# Sensor_Box_CAN_Switch_STM.net
KiCad netlist of a schematic drawn in Altium Designer
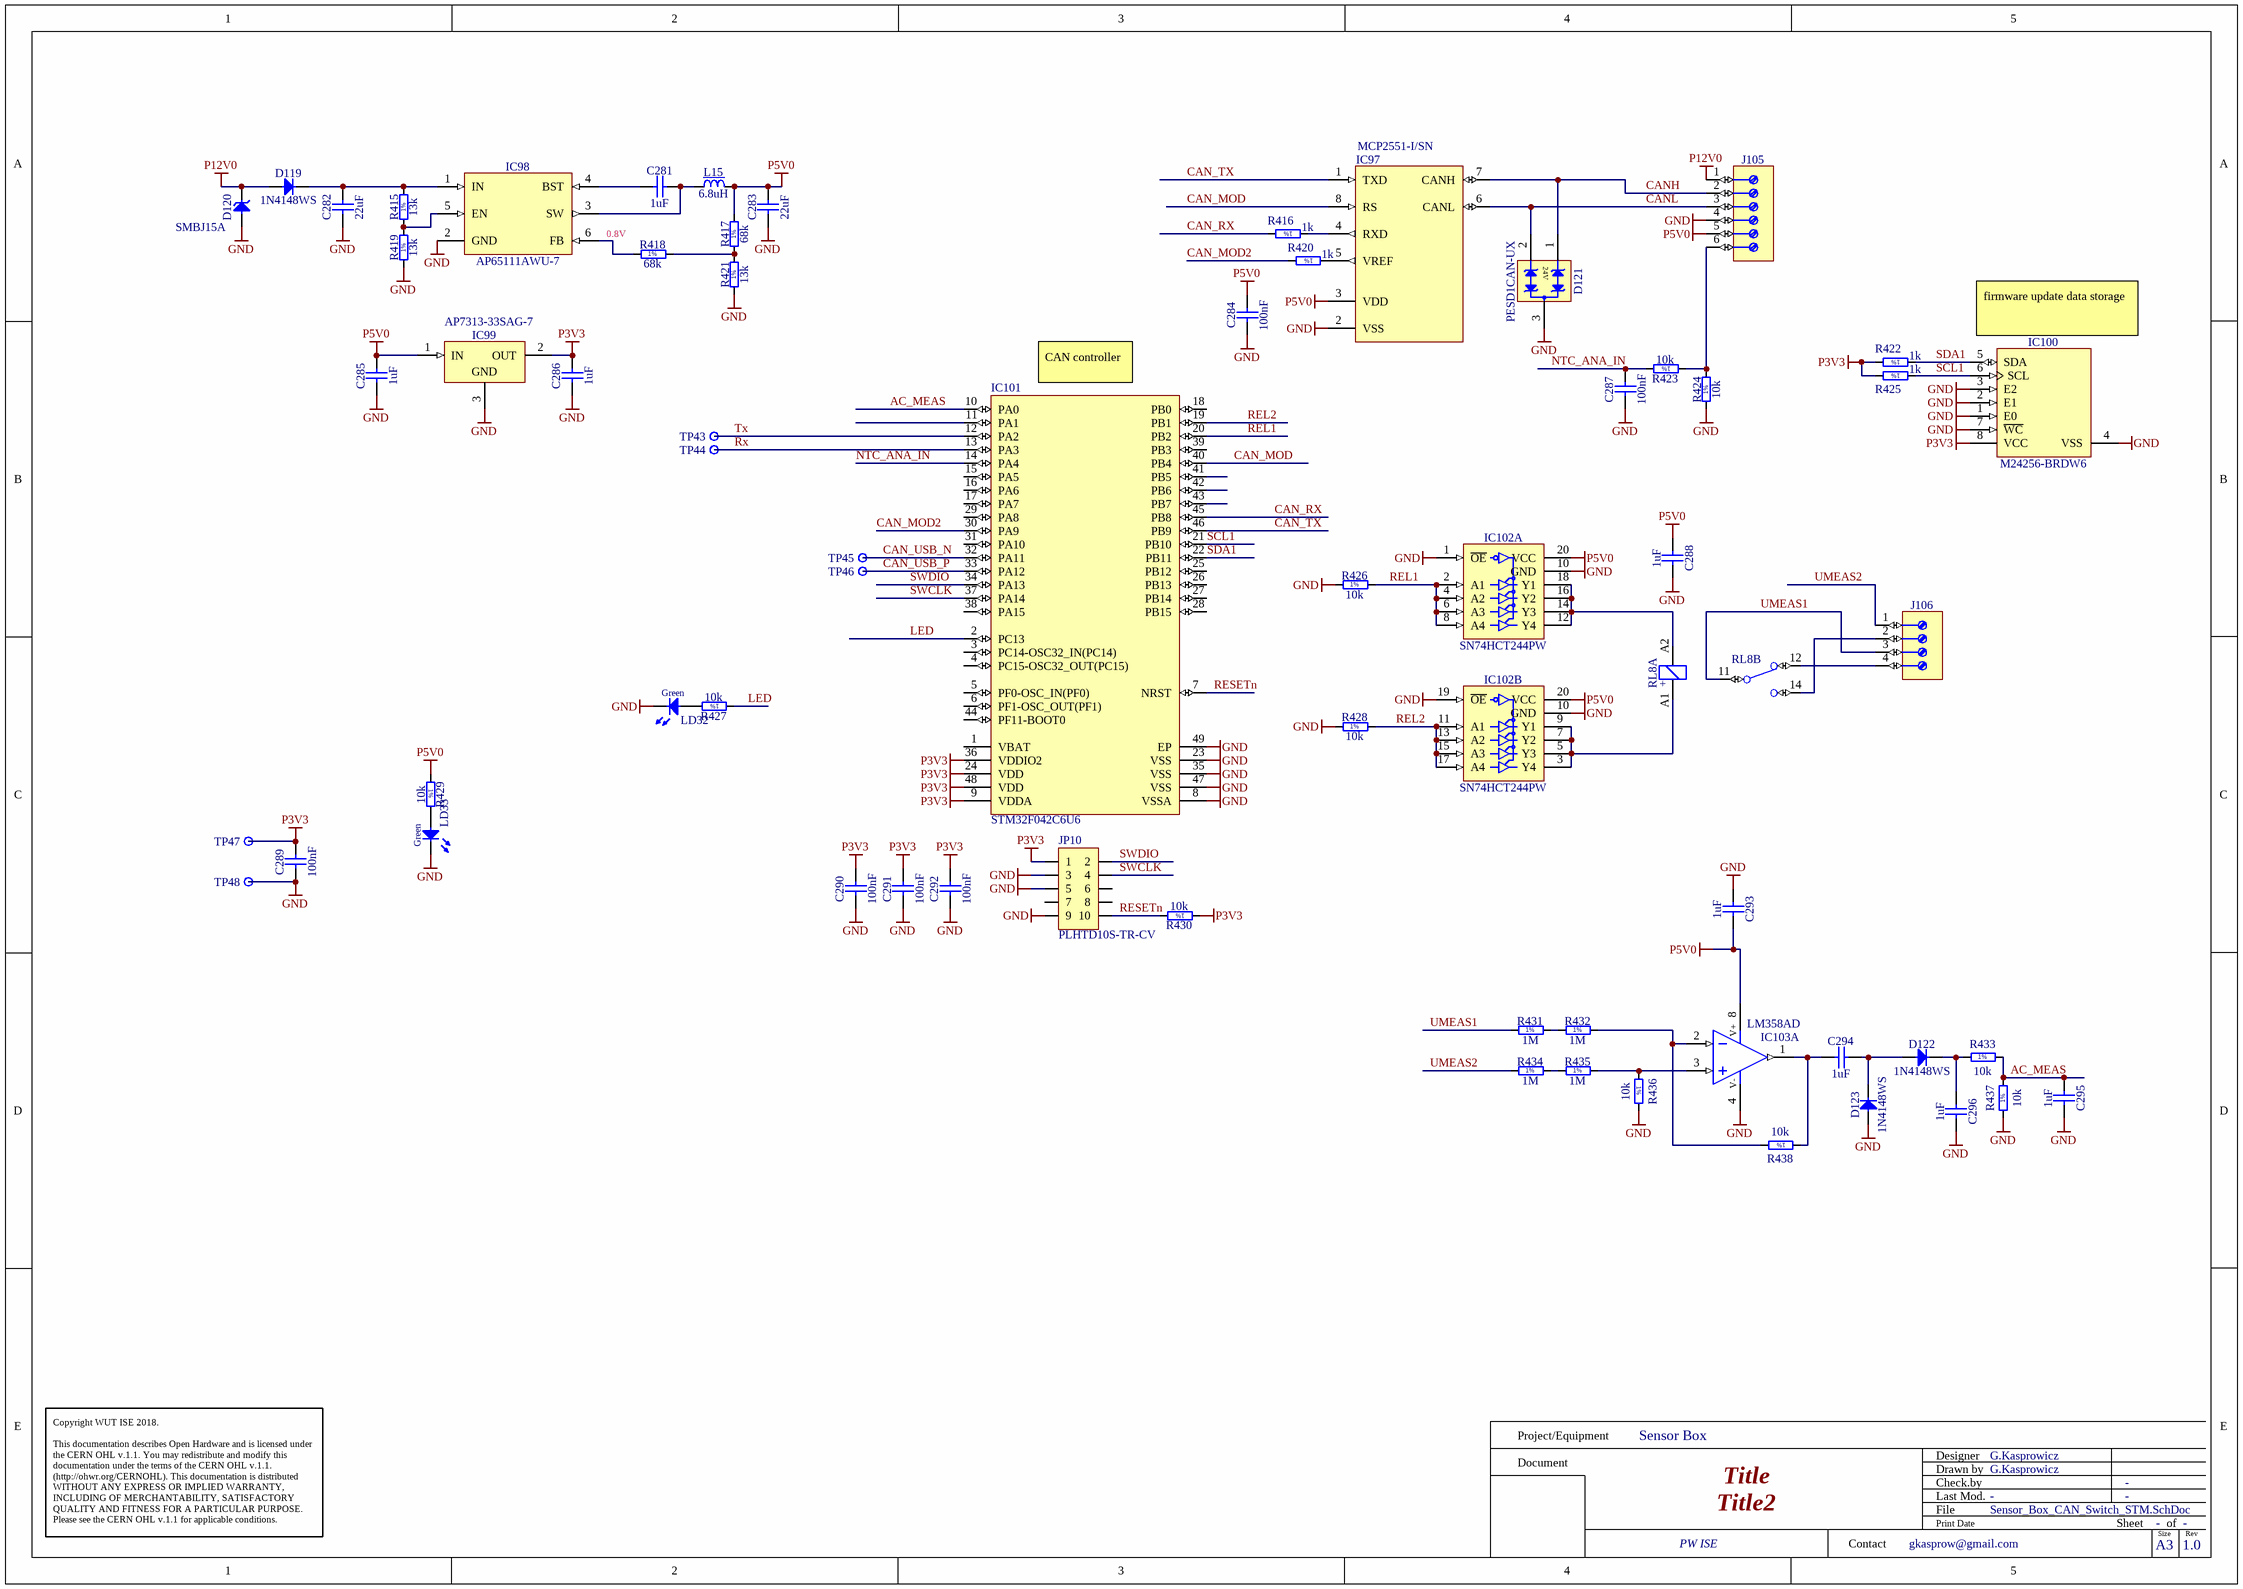
[diagram p0: Sensor_Box_CAN_Switch_STM.SchDoc]

(export (version "E")
  (design (tool "Eeschema 10.0.6"))
  (components
    (comp (ref "C281")
      (value "1uF")
      (footprint "CAPC1005X55N")
      (description "Non-polarised capacitor")
      (fields
        (field (name "PART NUMBER") "CC0402_1UF_16V_10%_X5R")
        (field (name "VOLTAGE") "16V")
        (field (name "AUTHOR") "CERN DEM JLC")
      )
      (libsource (lib "Capacitors") (part "Capacitor - non polarized"))
    )
    (comp (ref "C282")
      (value "22uF")
      (footprint "CAPC1709X100N")
      (description "Non-polarised capacitor")
      (fields
        (field (name "PART NUMBER") "CC0603_22UF_6.3V_20%_X5R")
        (field (name "VOLTAGE") "6.3V")
        (field (name "AUTHOR") "CERN DEM JLC")
      )
      (libsource (lib "Capacitors") (part "Capacitor - non polarized"))
    )
    (comp (ref "C283")
      (value "22uF")
      (footprint "CAPC1709X100N")
      (description "Non-polarised capacitor")
      (fields
        (field (name "PART NUMBER") "CC0603_22UF_6.3V_20%_X5R")
        (field (name "VOLTAGE") "6.3V")
        (field (name "AUTHOR") "CERN DEM JLC")
      )
      (libsource (lib "Capacitors") (part "Capacitor - non polarized"))
    )
    (comp (ref "C284")
      (value "100nF")
      (footprint "CAPC1005X55N")
      (description "Non-polarised capacitor")
      (fields
        (field (name "PART NUMBER") "CC0402_100NF_16V_10%_X5R")
        (field (name "VOLTAGE") "16V")
        (field (name "AUTHOR") "CERN DEM JLC")
      )
      (libsource (lib "Capacitors") (part "Capacitor - non polarized"))
    )
    (comp (ref "C285")
      (value "1uF")
      (footprint "CAPC1005X55N")
      (description "Non-polarised capacitor")
      (fields
        (field (name "PART NUMBER") "CC0402_1UF_16V_10%_X5R")
        (field (name "VOLTAGE") "16V")
        (field (name "AUTHOR") "CERN DEM JLC")
      )
      (libsource (lib "Capacitors") (part "Capacitor - non polarized"))
    )
    (comp (ref "C286")
      (value "1uF")
      (footprint "CAPC1005X55N")
      (description "Non-polarised capacitor")
      (fields
        (field (name "PART NUMBER") "CC0402_1UF_16V_10%_X5R")
        (field (name "VOLTAGE") "16V")
        (field (name "AUTHOR") "CERN DEM JLC")
      )
      (libsource (lib "Capacitors") (part "Capacitor - non polarized"))
    )
    (comp (ref "C287")
      (value "100nF")
      (footprint "CAPC1005X55N")
      (description "Non-polarised capacitor")
      (fields
        (field (name "PART NUMBER") "CC0402_100NF_16V_10%_X5R")
        (field (name "VOLTAGE") "16V")
        (field (name "AUTHOR") "CERN DEM JLC")
      )
      (libsource (lib "Capacitors") (part "Capacitor - non polarized"))
    )
    (comp (ref "C288")
      (value "1uF")
      (footprint "CAPC1005X55N")
      (description "Non-polarised capacitor")
      (fields
        (field (name "PART NUMBER") "CC0402_1UF_16V_10%_X5R")
        (field (name "VOLTAGE") "16V")
        (field (name "AUTHOR") "CERN DEM JLC")
      )
      (libsource (lib "Capacitors") (part "Capacitor - non polarized"))
    )
    (comp (ref "C289")
      (value "100nF")
      (footprint "CAPC1005X55N")
      (description "Non-polarised capacitor")
      (fields
        (field (name "PART NUMBER") "CC0402_100NF_16V_10%_X5R")
        (field (name "VOLTAGE") "16V")
        (field (name "AUTHOR") "CERN DEM JLC")
      )
      (libsource (lib "Capacitors") (part "Capacitor - non polarized"))
    )
    (comp (ref "C290")
      (value "100nF")
      (footprint "CAPC1005X55N")
      (description "Non-polarised capacitor")
      (fields
        (field (name "PART NUMBER") "CC0402_100NF_16V_10%_X5R")
        (field (name "VOLTAGE") "16V")
        (field (name "AUTHOR") "CERN DEM JLC")
      )
      (libsource (lib "Capacitors") (part "Capacitor - non polarized"))
    )
    (comp (ref "C291")
      (value "100nF")
      (footprint "CAPC1005X55N")
      (description "Non-polarised capacitor")
      (fields
        (field (name "PART NUMBER") "CC0402_100NF_16V_10%_X5R")
        (field (name "VOLTAGE") "16V")
        (field (name "AUTHOR") "CERN DEM JLC")
      )
      (libsource (lib "Capacitors") (part "Capacitor - non polarized"))
    )
    (comp (ref "C292")
      (value "100nF")
      (footprint "CAPC1005X55N")
      (description "Non-polarised capacitor")
      (fields
        (field (name "PART NUMBER") "CC0402_100NF_16V_10%_X5R")
        (field (name "VOLTAGE") "16V")
        (field (name "AUTHOR") "CERN DEM JLC")
      )
      (libsource (lib "Capacitors") (part "Capacitor - non polarized"))
    )
    (comp (ref "C293")
      (value "1uF")
      (footprint "CAPC1005X55N")
      (description "Non-polarised capacitor")
      (fields
        (field (name "PART NUMBER") "CC0402_1UF_16V_10%_X5R")
        (field (name "VOLTAGE") "16V")
        (field (name "AUTHOR") "CERN DEM JLC")
      )
      (libsource (lib "Capacitors") (part "Capacitor - non polarized"))
    )
    (comp (ref "C294")
      (value "1uF")
      (footprint "CAPC1005X55N")
      (description "Non-polarised capacitor")
      (fields
        (field (name "PART NUMBER") "CC0402_1UF_16V_10%_X5R")
        (field (name "VOLTAGE") "16V")
        (field (name "AUTHOR") "CERN DEM JLC")
      )
      (libsource (lib "Capacitors") (part "Capacitor - non polarized"))
    )
    (comp (ref "C295")
      (value "1uF")
      (footprint "CAPC1005X55N")
      (description "Non-polarised capacitor")
      (fields
        (field (name "PART NUMBER") "CC0402_1UF_16V_10%_X5R")
        (field (name "VOLTAGE") "16V")
        (field (name "AUTHOR") "CERN DEM JLC")
      )
      (libsource (lib "Capacitors") (part "Capacitor - non polarized"))
    )
    (comp (ref "C296")
      (value "1uF")
      (footprint "CAPC1005X55N")
      (description "Non-polarised capacitor")
      (fields
        (field (name "PART NUMBER") "CC0402_1UF_16V_10%_X5R")
        (field (name "VOLTAGE") "16V")
        (field (name "AUTHOR") "CERN DEM JLC")
      )
      (libsource (lib "Capacitors") (part "Capacitor - non polarized"))
    )
    (comp (ref "D119")
      (value "1N4148WS")
      (footprint "SODFL2512X100N")
      (description "Diode")
      (fields
        (field (name "VOLTAGE") "75V")
        (field (name "POWER") "150mA")
        (field (name "AUTHOR") "CERN DEM JLC")
      )
      (libsource (lib "ICs And Semiconductors") (part "Diode"))
    )
    (comp (ref "D120")
      (value "SMBJ15A")
      (footprint "DIOM5336X265N")
      (description "Zener Diode")
      (fields
        (field (name "VOLTAGE") "15V")
        (field (name "POWER") "600W")
        (field (name "AUTHOR") "CERN DEM JLC")
      )
      (libsource (lib "ICs And Semiconductors") (part "Diode Zener"))
    )
    (comp (ref "D121")
      (value "PESD1CAN-UX")
      (footprint "SOT95P237X112-3N")
      (description "TVS Diode for CAN")
      (fields
        (field (name "VOLTAGE") "24V")
        (field (name "POWER") "400W")
        (field (name "AUTHOR") "CERN DEM JLC")
      )
      (libsource (lib "LIBRARY_SCH") (part "D_TVS_PESD1CAN"))
    )
    (comp (ref "D122")
      (value "1N4148WS")
      (footprint "SODFL2512X100N")
      (description "Diode")
      (fields
        (field (name "VOLTAGE") "75V")
        (field (name "POWER") "150mA")
        (field (name "AUTHOR") "CERN DEM JLC")
      )
      (libsource (lib "ICs And Semiconductors") (part "Diode"))
    )
    (comp (ref "D123")
      (value "1N4148WS")
      (footprint "SODFL2512X100N")
      (description "Diode")
      (fields
        (field (name "VOLTAGE") "75V")
        (field (name "POWER") "150mA")
        (field (name "AUTHOR") "CERN DEM JLC")
      )
      (libsource (lib "ICs And Semiconductors") (part "Diode"))
    )
    (comp (ref "IC97")
      (value "MCP2551-I/SN")
      (footprint "SOIC127P600X175-8N")
      (description "High-Speed CAN Transceiver, 8-Pin SOIC, Industrial Temperature")
      (fields (field (name "MANUFACTURER") "MICROCHIP TECHNOLOGY") (field (name "AUTHOR") "GK"))
      (libsource (lib "LIBRARY_SCH") (part "IFC_MCP2551"))
    )
    (comp (ref "IC98")
      (value "AP65111AWU-7")
      (footprint "SOT95P280X100-6N")
      (description "Light Load Improved 1.5A Synch DC/DC Buck Converter")
      (fields (field (name "MANUFACTURER") "DIODES INCORPORATED") (field (name "AUTHOR") "CERN DEM JLC"))
      (libsource (lib "ICs And Semiconductors") (part "AP65111A"))
    )
    (comp (ref "IC99")
      (value "AP7313-33SAG-7")
      (footprint "SOT95P240X130-3N")
      (description "3-Terminal Regulator 1=IN 2=OUT 3=GND")
      (fields (field (name "MANUFACTURER") "DIODES INCORPORATED") (field (name "AUTHOR") "CERN DEM JLC"))
      (libsource (lib "ICs And Semiconductors") (part "REG3 1IN-2OUT-3GND"))
    )
    (comp (ref "IC100")
      (value "M24256-BRDW6")
      (footprint "SOP65P640X120-8N")
      (description "256-Kbit Serial I²C Bus EEPROM")
      (fields
        (field (name "PART NUMBER") "M24256-BRDW6P")
        (field (name "MANUFACTURER") "ST MICROELECTRONICS")
        (field (name "AUTHOR") "CERN DEM MR")
      )
      (libsource (lib "LIBRARY_SCH") (part "MEM_M24256-BRDW6P"))
    )
    (comp (ref "IC101")
      (value "STM32F042C6U6")
      (footprint "STM-UFQFPN48_L")
      (libsource (lib "Altium Content Vault") (part "MC-ARM-STM32F042-UFQFPN48"))
    )
    (comp (ref "IC102")
      (value "SN74HCT244PW")
      (footprint "SOP65P640X120-20N")
      (description "Octal Buffer/Driver with 3-State Ouputs")
      (fields (field (name "MANUFACTURER") "TEXAS INSTRUMENTS") (field (name "AUTHOR") "CERN DEM JLC"))
      (libsource (lib "ICs And Semiconductors") (part "74244_a"))
    )
    (comp (ref "IC103")
      (value "LM358AD")
      (footprint "SOIC127P600X175-8N")
      (description "Dual Operational Amplifier")
      (fields (field (name "MANUFACTURER") "TEXAS INSTRUMENTS") (field (name "AUTHOR") "CERN DEM JLC"))
      (libsource (lib "ICs And Semiconductors") (part "Operational Amplifier x2 Type1"))
    )
    (comp (ref "J105")
      (value "~")
      (footprint "PHOENIX_1725698")
      (description "Terminal Block, 6 Positions, Screw Connection")
      (fields
        (field (name "PART NUMBER") "PHOENIX_1725698")
        (field (name "MANUFACTURER") "PHOENIX CONTACT")
        (field (name "AUTHOR") "CERN DEM JMW")
      )
      (libsource (lib "Connectors") (part "Terminal Block_6 Positions_Screw Connection"))
    )
    (comp (ref "J106")
      (value "~")
      (footprint "TYCO_282836-4")
      (description "Terminal Block, 4 Positions, Screw Connection")
      (fields
        (field (name "PART NUMBER") "TYCO_282836-4")
        (field (name "MANUFACTURER") "TYCO ELECTRONICS")
        (field (name "AUTHOR") "CERN DEM JLC")
      )
      (libsource (lib "Connectors") (part "Terminal Block_4 Positions_Screw Connection"))
    )
    (comp (ref "JP10")
      (value "PLHTD10S-TR-CV")
      (footprint "PLHTD10S-TR-CV")
      (description "1.27 mm dual row goldpin (Maritex)")
      (libsource (lib "LIBRARY_SCH") (part "CON_2x5 1.27 SMT Male"))
    )
    (comp (ref "L15")
      (value "6.8uH")
      (footprint "IND_WALSIN_WLPN3030")
      (description "6,8uH; 900mA; 0,211Ω; 3x3x1,5mm")
      (fields
        (field (name "PART NUMBER") "IND_6.8UH_20%_WALSIN_WLPN303015M6R8PB")
        (field (name "POWER") "900mA")
        (field (name "AUTHOR") "GK")
      )
      (libsource (lib "LIBRARY_SCH") (part "IND_WLPN3030"))
    )
    (comp (ref "LD32")
      (value "Green")
      (footprint "LED_KINGBRIGHT_KPH-1608CGCK")
      (description "LED Green 1C 2A")
      (fields
        (field (name "PART NUMBER") "LED_KINGBRIGHT_KPH-1608CGCK")
        (field (name "MANUFACTURER") "KINGBRIGHT")
        (field (name "AUTHOR") "CERN DEM JLC")
      )
      (libsource (lib "ICs And Semiconductors") (part "LED Green 1C 2A"))
    )
    (comp (ref "LD33")
      (value "Green")
      (footprint "LED_KINGBRIGHT_KPH-1608CGCK")
      (description "LED Green 1C 2A")
      (fields
        (field (name "PART NUMBER") "LED_KINGBRIGHT_KPH-1608CGCK")
        (field (name "MANUFACTURER") "KINGBRIGHT")
        (field (name "AUTHOR") "CERN DEM JLC")
      )
      (libsource (lib "ICs And Semiconductors") (part "LED Green 1C 2A"))
    )
    (comp (ref "R415")
      (value "13k")
      (footprint "RESC1005X40N")
      (description "Resistor - 1%")
      (fields
        (field (name "PART NUMBER") "R0402_13K_1%_0.0625W_100PPM")
        (field (name "POWER") "0.0625W")
        (field (name "AUTHOR") "CERN DEM JLC")
      )
      (libsource (lib "Resistors") (part "Resistor - 1%"))
    )
    (comp (ref "R416")
      (value "1k")
      (footprint "RESC1005X40N")
      (description "Resistor - 1%")
      (fields
        (field (name "PART NUMBER") "R0402_1K_1%_0.0625W_100PPM")
        (field (name "POWER") "0.0625W")
        (field (name "AUTHOR") "CERN DEM JLC")
      )
      (libsource (lib "Resistors") (part "Resistor - 1%"))
    )
    (comp (ref "R417")
      (value "68k")
      (footprint "RESC1005X40N")
      (description "Resistor - 1%")
      (fields
        (field (name "PART NUMBER") "R0402_68K_1%_0.0625W_100PPM")
        (field (name "POWER") "0.0625W")
        (field (name "AUTHOR") "CERN DEM JLC")
      )
      (libsource (lib "Resistors") (part "Resistor - 1%"))
    )
    (comp (ref "R418")
      (value "68k")
      (footprint "RESC1005X40N")
      (description "Resistor - 1%")
      (fields
        (field (name "PART NUMBER") "R0402_68K_1%_0.0625W_100PPM")
        (field (name "POWER") "0.0625W")
        (field (name "AUTHOR") "CERN DEM JLC")
      )
      (libsource (lib "Resistors") (part "Resistor - 1%"))
    )
    (comp (ref "R419")
      (value "13k")
      (footprint "RESC1005X40N")
      (description "Resistor - 1%")
      (fields
        (field (name "PART NUMBER") "R0402_13K_1%_0.0625W_100PPM")
        (field (name "POWER") "0.0625W")
        (field (name "AUTHOR") "CERN DEM JLC")
      )
      (libsource (lib "Resistors") (part "Resistor - 1%"))
    )
    (comp (ref "R420")
      (value "1k")
      (footprint "RESC1005X40N")
      (description "Resistor - 1%")
      (fields
        (field (name "PART NUMBER") "R0402_1K_1%_0.0625W_100PPM")
        (field (name "POWER") "0.0625W")
        (field (name "AUTHOR") "CERN DEM JLC")
      )
      (libsource (lib "Resistors") (part "Resistor - 1%"))
    )
    (comp (ref "R421")
      (value "13k")
      (footprint "RESC1005X40N")
      (description "Resistor - 1%")
      (fields
        (field (name "PART NUMBER") "R0402_13K_1%_0.0625W_100PPM")
        (field (name "POWER") "0.0625W")
        (field (name "AUTHOR") "CERN DEM JLC")
      )
      (libsource (lib "Resistors") (part "Resistor - 1%"))
    )
    (comp (ref "R422")
      (value "1k")
      (footprint "RESC1005X40N")
      (description "Resistor - 1%")
      (fields
        (field (name "PART NUMBER") "R0402_1K_1%_0.0625W_100PPM")
        (field (name "POWER") "0.0625W")
        (field (name "AUTHOR") "CERN DEM JLC")
      )
      (libsource (lib "Resistors") (part "Resistor - 1%"))
    )
    (comp (ref "R423")
      (value "10k")
      (footprint "RESC1005X40N")
      (description "Resistor - 1%")
      (fields
        (field (name "PART NUMBER") "R0402_10K_1%_0.0625W_100PPM")
        (field (name "POWER") "0.0625W")
        (field (name "AUTHOR") "CERN DEM JLC")
      )
      (libsource (lib "Resistors") (part "Resistor - 1%"))
    )
    (comp (ref "R424")
      (value "10k")
      (footprint "RESC1005X40N")
      (description "Resistor - 1%")
      (fields
        (field (name "PART NUMBER") "R0402_10K_1%_0.0625W_100PPM")
        (field (name "POWER") "0.0625W")
        (field (name "AUTHOR") "CERN DEM JLC")
      )
      (libsource (lib "Resistors") (part "Resistor - 1%"))
    )
    (comp (ref "R425")
      (value "1k")
      (footprint "RESC1005X40N")
      (description "Resistor - 1%")
      (fields
        (field (name "PART NUMBER") "R0402_1K_1%_0.0625W_100PPM")
        (field (name "POWER") "0.0625W")
        (field (name "AUTHOR") "CERN DEM JLC")
      )
      (libsource (lib "Resistors") (part "Resistor - 1%"))
    )
    (comp (ref "R426")
      (value "10k")
      (footprint "RESC1005X40N")
      (description "Resistor - 1%")
      (fields
        (field (name "PART NUMBER") "R0402_10K_1%_0.0625W_100PPM")
        (field (name "POWER") "0.0625W")
        (field (name "AUTHOR") "CERN DEM JLC")
      )
      (libsource (lib "Resistors") (part "Resistor - 1%"))
    )
    (comp (ref "R427")
      (value "10k")
      (footprint "RESC1005X40N")
      (description "Resistor - 1%")
      (fields
        (field (name "PART NUMBER") "R0402_10K_1%_0.0625W_100PPM")
        (field (name "POWER") "0.0625W")
        (field (name "AUTHOR") "CERN DEM JLC")
      )
      (libsource (lib "Resistors") (part "Resistor - 1%"))
    )
    (comp (ref "R428")
      (value "10k")
      (footprint "RESC1005X40N")
      (description "Resistor - 1%")
      (fields
        (field (name "PART NUMBER") "R0402_10K_1%_0.0625W_100PPM")
        (field (name "POWER") "0.0625W")
        (field (name "AUTHOR") "CERN DEM JLC")
      )
      (libsource (lib "Resistors") (part "Resistor - 1%"))
    )
    (comp (ref "R429")
      (value "10k")
      (footprint "RESC1005X40N")
      (description "Resistor - 1%")
      (fields
        (field (name "PART NUMBER") "R0402_10K_1%_0.0625W_100PPM")
        (field (name "POWER") "0.0625W")
        (field (name "AUTHOR") "CERN DEM JLC")
      )
      (libsource (lib "Resistors") (part "Resistor - 1%"))
    )
    (comp (ref "R430")
      (value "10k")
      (footprint "RESC1005X40N")
      (description "Resistor - 1%")
      (fields
        (field (name "PART NUMBER") "R0402_10K_1%_0.0625W_100PPM")
        (field (name "POWER") "0.0625W")
        (field (name "AUTHOR") "CERN DEM JLC")
      )
      (libsource (lib "Resistors") (part "Resistor - 1%"))
    )
    (comp (ref "R431")
      (value "1M")
      (footprint "RESC3216X65N")
      (description "Resistor - 1%")
      (fields
        (field (name "PART NUMBER") "R1206_1M_1%_0.25W_100PPM")
        (field (name "POWER") "0.25W")
        (field (name "AUTHOR") "CERN DEM JLC")
      )
      (libsource (lib "Resistors") (part "Resistor - 1%"))
    )
    (comp (ref "R432")
      (value "1M")
      (footprint "RESC3216X65N")
      (description "Resistor - 1%")
      (fields
        (field (name "PART NUMBER") "R1206_1M_1%_0.25W_100PPM")
        (field (name "POWER") "0.25W")
        (field (name "AUTHOR") "CERN DEM JLC")
      )
      (libsource (lib "Resistors") (part "Resistor - 1%"))
    )
    (comp (ref "R433")
      (value "10k")
      (footprint "RESC1005X40N")
      (description "Resistor - 1%")
      (fields
        (field (name "PART NUMBER") "R0402_10K_1%_0.0625W_100PPM")
        (field (name "POWER") "0.0625W")
        (field (name "AUTHOR") "CERN DEM JLC")
      )
      (libsource (lib "Resistors") (part "Resistor - 1%"))
    )
    (comp (ref "R434")
      (value "1M")
      (footprint "RESC3216X65N")
      (description "Resistor - 1%")
      (fields
        (field (name "PART NUMBER") "R1206_1M_1%_0.25W_100PPM")
        (field (name "POWER") "0.25W")
        (field (name "AUTHOR") "CERN DEM JLC")
      )
      (libsource (lib "Resistors") (part "Resistor - 1%"))
    )
    (comp (ref "R435")
      (value "1M")
      (footprint "RESC3216X65N")
      (description "Resistor - 1%")
      (fields
        (field (name "PART NUMBER") "R1206_1M_1%_0.25W_100PPM")
        (field (name "POWER") "0.25W")
        (field (name "AUTHOR") "CERN DEM JLC")
      )
      (libsource (lib "Resistors") (part "Resistor - 1%"))
    )
    (comp (ref "R436")
      (value "10k")
      (footprint "RESC1005X40N")
      (description "Resistor - 1%")
      (fields
        (field (name "PART NUMBER") "R0402_10K_1%_0.0625W_100PPM")
        (field (name "POWER") "0.0625W")
        (field (name "AUTHOR") "CERN DEM JLC")
      )
      (libsource (lib "Resistors") (part "Resistor - 1%"))
    )
    (comp (ref "R437")
      (value "10k")
      (footprint "RESC1005X40N")
      (description "Resistor - 1%")
      (fields
        (field (name "PART NUMBER") "R0402_10K_1%_0.0625W_100PPM")
        (field (name "POWER") "0.0625W")
        (field (name "AUTHOR") "CERN DEM JLC")
      )
      (libsource (lib "Resistors") (part "Resistor - 1%"))
    )
    (comp (ref "R438")
      (value "10k")
      (footprint "RESC1005X40N")
      (description "Resistor - 1%")
      (fields
        (field (name "PART NUMBER") "R0402_10K_1%_0.0625W_100PPM")
        (field (name "POWER") "0.0625W")
        (field (name "AUTHOR") "CERN DEM JLC")
      )
      (libsource (lib "Resistors") (part "Resistor - 1%"))
    )
    (comp (ref "RL8")
      (value "REL_TYCO_PE01")
      (footprint "REL_TYCO_PE01")
      (description "1 form C (CO) General Purpose Low Power PCB Relay, PE Series")
      (fields
        (field (name "PART NUMBER") "REL_TYCO_PE014F05")
        (field (name "MANUFACTURER") "TYCO SCHRACK")
        (field (name "AUTHOR") "CERN DEM JLC")
      )
      (libsource (lib "") (part "REL_TYCO_PE01_1"))
    )
    (comp (ref "TP43")
      (value "Test Point")
      (footprint "TPS127")
      (fields (field (name "PART NUMBER") "SMD_PAD_1.27X1.27MM") (field (name "AUTHOR") "CERN DEM JLC"))
      (libsource (lib "Eletro-mechanical") (part "Test Point"))
    )
    (comp (ref "TP44")
      (value "Test Point")
      (footprint "TPS127")
      (fields (field (name "PART NUMBER") "SMD_PAD_1.27X1.27MM") (field (name "AUTHOR") "CERN DEM JLC"))
      (libsource (lib "Eletro-mechanical") (part "Test Point"))
    )
    (comp (ref "TP45")
      (value "Test Point")
      (footprint "TPS127")
      (fields (field (name "PART NUMBER") "SMD_PAD_1.27X1.27MM") (field (name "AUTHOR") "CERN DEM JLC"))
      (libsource (lib "Eletro-mechanical") (part "Test Point"))
    )
    (comp (ref "TP46")
      (value "Test Point")
      (footprint "TPS127")
      (fields (field (name "PART NUMBER") "SMD_PAD_1.27X1.27MM") (field (name "AUTHOR") "CERN DEM JLC"))
      (libsource (lib "Eletro-mechanical") (part "Test Point"))
    )
    (comp (ref "TP47")
      (value "Test Point")
      (footprint "TPS127")
      (fields (field (name "PART NUMBER") "SMD_PAD_1.27X1.27MM") (field (name "AUTHOR") "CERN DEM JLC"))
      (libsource (lib "Eletro-mechanical") (part "Test Point"))
    )
    (comp (ref "TP48")
      (value "Test Point")
      (footprint "TPS127")
      (fields (field (name "PART NUMBER") "SMD_PAD_1.27X1.27MM") (field (name "AUTHOR") "CERN DEM JLC"))
      (libsource (lib "Eletro-mechanical") (part "Test Point"))
    )
  )
  (nets
    (net (code "1") (name "/AC_MEAS") (class "Default")
      (node (ref "C295") (pin "1") (pinfunction "1_1") (pintype "passive"))
      (node (ref "IC101") (pin "10") (pinfunction "PA0_10") (pintype "bidirectional"))
      (node (ref "R433") (pin "2") (pinfunction "2_2") (pintype "passive"))
      (node (ref "R437") (pin "2") (pinfunction "2_2") (pintype "passive"))
    )
    (net (code "2") (name "/CANH") (class "Default")
      (node (ref "D121") (pin "1") (pinfunction "I/O1_1") (pintype "passive"))
      (node (ref "IC97") (pin "7") (pinfunction "CANH_7") (pintype "bidirectional"))
      (node (ref "J105") (pin "2") (pinfunction "2_2") (pintype "bidirectional"))
    )
    (net (code "3") (name "/CANL") (class "Default")
      (node (ref "D121") (pin "2") (pinfunction "I/O2_2") (pintype "passive"))
      (node (ref "IC97") (pin "6") (pinfunction "CANL_6") (pintype "bidirectional"))
      (node (ref "J105") (pin "3") (pinfunction "3_3") (pintype "bidirectional"))
    )
    (net (code "4") (name "/CAN_MOD") (class "Default")
      (node (ref "IC101") (pin "40") (pinfunction "PB4_40") (pintype "bidirectional"))
      (node (ref "IC97") (pin "8") (pinfunction "RS_8") (pintype "input"))
    )
    (net (code "5") (name "/CAN_MOD2") (class "Default")
      (node (ref "IC101") (pin "30") (pinfunction "PA9_30") (pintype "bidirectional"))
      (node (ref "R420") (pin "2") (pinfunction "2_2") (pintype "passive"))
    )
    (net (code "6") (name "/CAN_RX") (class "Default")
      (node (ref "IC101") (pin "45") (pinfunction "PB8_45") (pintype "bidirectional"))
      (node (ref "R416") (pin "2") (pinfunction "2_2") (pintype "passive"))
    )
    (net (code "7") (name "/CAN_TX") (class "Default")
      (node (ref "IC101") (pin "46") (pinfunction "PB9_46") (pintype "bidirectional"))
      (node (ref "IC97") (pin "1") (pinfunction "TXD_1") (pintype "input"))
    )
    (net (code "8") (name "/CAN_USB_N") (class "Default")
      (node (ref "IC101") (pin "32") (pinfunction "PA11_32") (pintype "bidirectional"))
      (node (ref "TP45") (pin "1") (pinfunction "1_1") (pintype "bidirectional"))
    )
    (net (code "9") (name "/CAN_USB_P") (class "Default")
      (node (ref "IC101") (pin "33") (pinfunction "PA12_33") (pintype "bidirectional"))
      (node (ref "TP46") (pin "1") (pinfunction "1_1") (pintype "bidirectional"))
    )
    (net (code "10") (name "/LED") (class "Default")
      (node (ref "IC101") (pin "2") (pinfunction "PC13_2") (pintype "bidirectional"))
      (node (ref "R427") (pin "1") (pinfunction "1_1") (pintype "passive"))
    )
    (net (code "11") (name "/NTC_ANA_IN") (class "Default")
      (node (ref "C287") (pin "2") (pinfunction "2_2") (pintype "passive"))
      (node (ref "IC101") (pin "14") (pinfunction "PA4_14") (pintype "bidirectional"))
      (node (ref "R423") (pin "2") (pinfunction "2_2") (pintype "passive"))
    )
    (net (code "12") (name "/REL1") (class "Default")
      (node (ref "IC101") (pin "20") (pinfunction "PB2_20") (pintype "bidirectional"))
      (node (ref "IC102") (pin "2") (pinfunction "A1_2") (pintype "input"))
      (node (ref "IC102") (pin "4") (pinfunction "A2_4") (pintype "input"))
      (node (ref "IC102") (pin "6") (pinfunction "A3_6") (pintype "input"))
      (node (ref "IC102") (pin "8") (pinfunction "A4_8") (pintype "input"))
      (node (ref "R426") (pin "2") (pinfunction "2_2") (pintype "passive"))
    )
    (net (code "13") (name "/REL2") (class "Default")
      (node (ref "IC101") (pin "19") (pinfunction "PB1_19") (pintype "bidirectional"))
      (node (ref "IC102") (pin "11") (pinfunction "A1_11") (pintype "input"))
      (node (ref "IC102") (pin "13") (pinfunction "A2_13") (pintype "input"))
      (node (ref "IC102") (pin "15") (pinfunction "A3_15") (pintype "input"))
      (node (ref "IC102") (pin "17") (pinfunction "A4_17") (pintype "input"))
      (node (ref "R428") (pin "2") (pinfunction "2_2") (pintype "passive"))
    )
    (net (code "14") (name "/RESETn") (class "Default")
      (node (ref "IC101") (pin "7") (pinfunction "NRST_7") (pintype "bidirectional"))
      (node (ref "JP10") (pin "10") (pinfunction "10_10") (pintype "passive"))
      (node (ref "R430") (pin "2") (pinfunction "2_2") (pintype "passive"))
    )
    (net (code "15") (name "/Rx") (class "Default")
      (node (ref "IC101") (pin "13") (pinfunction "PA3_13") (pintype "bidirectional"))
      (node (ref "TP44") (pin "1") (pinfunction "1_1") (pintype "bidirectional"))
    )
    (net (code "16") (name "/SCL1") (class "Default")
      (node (ref "IC100") (pin "6") (pinfunction "SCL_6") (pintype "input"))
      (node (ref "IC101") (pin "21") (pinfunction "PB10_21") (pintype "bidirectional"))
      (node (ref "R425") (pin "1") (pinfunction "1_1") (pintype "passive"))
    )
    (net (code "17") (name "/SDA1") (class "Default")
      (node (ref "IC100") (pin "5") (pinfunction "SDA_5") (pintype "bidirectional"))
      (node (ref "IC101") (pin "22") (pinfunction "PB11_22") (pintype "bidirectional"))
      (node (ref "R422") (pin "1") (pinfunction "1_1") (pintype "passive"))
    )
    (net (code "18") (name "/SWCLK") (class "Default")
      (node (ref "IC101") (pin "37") (pinfunction "PA14_37") (pintype "bidirectional"))
      (node (ref "JP10") (pin "4") (pinfunction "4_4") (pintype "passive"))
    )
    (net (code "19") (name "/SWDIO") (class "Default")
      (node (ref "IC101") (pin "34") (pinfunction "PA13_34") (pintype "bidirectional"))
      (node (ref "JP10") (pin "2") (pinfunction "2_2") (pintype "passive"))
    )
    (net (code "20") (name "/Tx") (class "Default")
      (node (ref "IC101") (pin "12") (pinfunction "PA2_12") (pintype "bidirectional"))
      (node (ref "TP43") (pin "1") (pinfunction "1_1") (pintype "bidirectional"))
    )
    (net (code "21") (name "/UMEAS1") (class "Default")
      (node (ref "J106") (pin "3") (pinfunction "3_3") (pintype "bidirectional"))
      (node (ref "R431") (pin "1") (pinfunction "1_1") (pintype "passive"))
      (node (ref "RL8") (pin "11") (pinfunction "C_11") (pintype "bidirectional"))
    )
    (net (code "22") (name "/UMEAS2") (class "Default")
      (node (ref "J106") (pin "1") (pinfunction "1_1") (pintype "bidirectional"))
      (node (ref "R434") (pin "1") (pinfunction "1_1") (pintype "passive"))
    )
    (net (code "23") (name "GND") (class "Default")
      (node (ref "C282") (pin "1") (pinfunction "1_1") (pintype "passive"))
      (node (ref "C283") (pin "1") (pinfunction "1_1") (pintype "passive"))
      (node (ref "C284") (pin "1") (pinfunction "1_1") (pintype "passive"))
      (node (ref "C285") (pin "1") (pinfunction "1_1") (pintype "passive"))
      (node (ref "C286") (pin "1") (pinfunction "1_1") (pintype "passive"))
      (node (ref "C287") (pin "1") (pinfunction "1_1") (pintype "passive"))
      (node (ref "C288") (pin "2") (pinfunction "2_2") (pintype "passive"))
      (node (ref "C289") (pin "1") (pinfunction "1_1") (pintype "passive"))
      (node (ref "C290") (pin "1") (pinfunction "1_1") (pintype "passive"))
      (node (ref "C291") (pin "1") (pinfunction "1_1") (pintype "passive"))
      (node (ref "C292") (pin "1") (pinfunction "1_1") (pintype "passive"))
      (node (ref "C293") (pin "1") (pinfunction "1_1") (pintype "passive"))
      (node (ref "C295") (pin "2") (pinfunction "2_2") (pintype "passive"))
      (node (ref "C296") (pin "2") (pinfunction "2_2") (pintype "passive"))
      (node (ref "D120") (pin "2") (pinfunction "A_2") (pintype "passive"))
      (node (ref "D121") (pin "3") (pinfunction "GND_3") (pintype "passive"))
      (node (ref "D123") (pin "2") (pinfunction "A_2") (pintype "passive"))
      (node (ref "IC100") (pin "1") (pinfunction "E0_1") (pintype "input"))
      (node (ref "IC100") (pin "2") (pinfunction "E1_2") (pintype "input"))
      (node (ref "IC100") (pin "3") (pinfunction "E2_3") (pintype "input"))
      (node (ref "IC100") (pin "4") (pinfunction "VSS_4") (pintype "power_in"))
      (node (ref "IC100") (pin "7") (pinfunction "~{WC}_7") (pintype "input"))
      (node (ref "IC101") (pin "23") (pinfunction "VSS_23") (pintype "power_in"))
      (node (ref "IC101") (pin "35") (pinfunction "VSS_35") (pintype "power_in"))
      (node (ref "IC101") (pin "47") (pinfunction "VSS_47") (pintype "power_in"))
      (node (ref "IC101") (pin "49") (pinfunction "EP_49") (pintype "power_in"))
      (node (ref "IC101") (pin "8") (pinfunction "VSSA_8") (pintype "power_in"))
      (node (ref "IC102") (pin "1") (pinfunction "~{OE}_1") (pintype "input"))
      (node (ref "IC102") (pin "10") (pinfunction "GND_10") (pintype "power_in"))
      (node (ref "IC102") (pin "19") (pinfunction "~{OE}_19") (pintype "input"))
      (node (ref "IC103") (pin "4") (pinfunction "V-_4") (pintype "power_in"))
      (node (ref "IC97") (pin "2") (pinfunction "VSS_2") (pintype "power_in"))
      (node (ref "IC98") (pin "2") (pinfunction "GND_2") (pintype "power_in"))
      (node (ref "IC99") (pin "3") (pinfunction "GND_3") (pintype "power_in"))
      (node (ref "J105") (pin "4") (pinfunction "4_4") (pintype "bidirectional"))
      (node (ref "JP10") (pin "3") (pinfunction "3_3") (pintype "passive"))
      (node (ref "JP10") (pin "5") (pinfunction "5_5") (pintype "passive"))
      (node (ref "JP10") (pin "9") (pinfunction "9_9") (pintype "passive"))
      (node (ref "LD32") (pin "1") (pinfunction "C_1") (pintype "passive"))
      (node (ref "LD33") (pin "1") (pinfunction "C_1") (pintype "passive"))
      (node (ref "R419") (pin "1") (pinfunction "1_1") (pintype "passive"))
      (node (ref "R421") (pin "1") (pinfunction "1_1") (pintype "passive"))
      (node (ref "R424") (pin "1") (pinfunction "1_1") (pintype "passive"))
      (node (ref "R426") (pin "1") (pinfunction "1_1") (pintype "passive"))
      (node (ref "R428") (pin "1") (pinfunction "1_1") (pintype "passive"))
      (node (ref "R436") (pin "2") (pinfunction "2_2") (pintype "passive"))
      (node (ref "R437") (pin "1") (pinfunction "1_1") (pintype "passive"))
      (node (ref "TP48") (pin "1") (pinfunction "1_1") (pintype "bidirectional"))
    )
    (net (code "24") (name "Net-(D119-C)") (class "Default")
      (node (ref "C282") (pin "2") (pinfunction "2_2") (pintype "passive"))
      (node (ref "D119") (pin "1") (pinfunction "C_1") (pintype "passive"))
      (node (ref "IC98") (pin "1") (pinfunction "IN_1") (pintype "input"))
      (node (ref "R415") (pin "2") (pinfunction "2_2") (pintype "passive"))
    )
    (net (code "25") (name "Net-(D122-A)") (class "Default")
      (node (ref "C294") (pin "2") (pinfunction "2_2") (pintype "passive"))
      (node (ref "D122") (pin "2") (pinfunction "A_2") (pintype "passive"))
      (node (ref "D123") (pin "1") (pinfunction "C_1") (pintype "passive"))
    )
    (net (code "26") (name "Net-(D122-C)") (class "Default")
      (node (ref "C296") (pin "1") (pinfunction "1_1") (pintype "passive"))
      (node (ref "D122") (pin "1") (pinfunction "C_1") (pintype "passive"))
      (node (ref "R433") (pin "1") (pinfunction "1_1") (pintype "passive"))
    )
    (net (code "27") (name "Net-(IC97-RXD)") (class "Default")
      (node (ref "IC97") (pin "4") (pinfunction "RXD_4") (pintype "output"))
      (node (ref "R416") (pin "1") (pinfunction "1_1") (pintype "passive"))
    )
    (net (code "28") (name "Net-(IC97-VREF)") (class "Default")
      (node (ref "IC97") (pin "5") (pinfunction "VREF_5") (pintype "output"))
      (node (ref "R420") (pin "1") (pinfunction "1_1") (pintype "passive"))
    )
    (net (code "29") (name "Net-(IC98-BST)") (class "Default")
      (node (ref "C281") (pin "1") (pinfunction "1_1") (pintype "passive"))
      (node (ref "IC98") (pin "4") (pinfunction "BST_4") (pintype "input"))
    )
    (net (code "30") (name "Net-(IC98-EN)") (class "Default")
      (node (ref "IC98") (pin "5") (pinfunction "EN_5") (pintype "input"))
      (node (ref "R415") (pin "1") (pinfunction "1_1") (pintype "passive"))
      (node (ref "R419") (pin "2") (pinfunction "2_2") (pintype "passive"))
    )
    (net (code "31") (name "Net-(IC98-FB)") (class "Default")
      (node (ref "IC98") (pin "6") (pinfunction "FB_6") (pintype "input"))
      (node (ref "R418") (pin "1") (pinfunction "1_1") (pintype "passive"))
    )
    (net (code "32") (name "Net-(IC98-SW)") (class "Default")
      (node (ref "C281") (pin "2") (pinfunction "2_2") (pintype "passive"))
      (node (ref "IC98") (pin "3") (pinfunction "SW_3") (pintype "output"))
      (node (ref "L15") (pin "1") (pinfunction "1_1") (pintype "passive"))
    )
    (net (code "33") (name "Net-(IC102A-Y1)") (class "Default")
      (node (ref "IC102") (pin "12") (pinfunction "Y4_12") (pintype "tri_state"))
      (node (ref "IC102") (pin "14") (pinfunction "Y3_14") (pintype "tri_state"))
      (node (ref "IC102") (pin "16") (pinfunction "Y2_16") (pintype "tri_state"))
      (node (ref "IC102") (pin "18") (pinfunction "Y1_18") (pintype "tri_state"))
      (node (ref "RL8") (pin "A2") (pinfunction "A2_A2") (pintype "passive"))
    )
    (net (code "34") (name "Net-(IC102B-Y1)") (class "Default")
      (node (ref "IC102") (pin "3") (pinfunction "Y4_3") (pintype "tri_state"))
      (node (ref "IC102") (pin "5") (pinfunction "Y3_5") (pintype "tri_state"))
      (node (ref "IC102") (pin "7") (pinfunction "Y2_7") (pintype "tri_state"))
      (node (ref "IC102") (pin "9") (pinfunction "Y1_9") (pintype "tri_state"))
      (node (ref "RL8") (pin "A1") (pinfunction "A1_A1") (pintype "passive"))
    )
    (net (code "35") (name "Net-(IC103A-IN+)") (class "Default")
      (node (ref "IC103") (pin "3") (pinfunction "IN+_3") (pintype "input"))
      (node (ref "R435") (pin "2") (pinfunction "2_2") (pintype "passive"))
      (node (ref "R436") (pin "1") (pinfunction "1_1") (pintype "passive"))
    )
    (net (code "36") (name "Net-(IC103A-IN-)") (class "Default")
      (node (ref "IC103") (pin "2") (pinfunction "IN-_2") (pintype "input"))
      (node (ref "R432") (pin "2") (pinfunction "2_2") (pintype "passive"))
      (node (ref "R438") (pin "2") (pinfunction "2_2") (pintype "passive"))
    )
    (net (code "37") (name "Net-(IC103A-OUT)") (class "Default")
      (node (ref "C294") (pin "1") (pinfunction "1_1") (pintype "passive"))
      (node (ref "IC103") (pin "1") (pinfunction "OUT_1") (pintype "output"))
      (node (ref "R438") (pin "1") (pinfunction "1_1") (pintype "passive"))
    )
    (net (code "38") (name "Net-(J105-Pad6)") (class "Default")
      (node (ref "J105") (pin "6") (pinfunction "6_6") (pintype "bidirectional"))
      (node (ref "R423") (pin "1") (pinfunction "1_1") (pintype "passive"))
      (node (ref "R424") (pin "2") (pinfunction "2_2") (pintype "passive"))
    )
    (net (code "39") (name "Net-(LD32-A)") (class "Default")
      (node (ref "LD32") (pin "2") (pinfunction "A_2") (pintype "passive"))
      (node (ref "R427") (pin "2") (pinfunction "2_2") (pintype "passive"))
    )
    (net (code "40") (name "Net-(LD33-A)") (class "Default")
      (node (ref "LD33") (pin "2") (pinfunction "A_2") (pintype "passive"))
      (node (ref "R429") (pin "2") (pinfunction "2_2") (pintype "passive"))
    )
    (net (code "41") (name "Net-(R417-Pad1)") (class "Default")
      (node (ref "R417") (pin "1") (pinfunction "1_1") (pintype "passive"))
      (node (ref "R418") (pin "2") (pinfunction "2_2") (pintype "passive"))
      (node (ref "R421") (pin "2") (pinfunction "2_2") (pintype "passive"))
    )
    (net (code "42") (name "Net-(R431-Pad2)") (class "Default")
      (node (ref "R431") (pin "2") (pinfunction "2_2") (pintype "passive"))
      (node (ref "R432") (pin "1") (pinfunction "1_1") (pintype "passive"))
    )
    (net (code "43") (name "Net-(R434-Pad2)") (class "Default")
      (node (ref "R434") (pin "2") (pinfunction "2_2") (pintype "passive"))
      (node (ref "R435") (pin "1") (pinfunction "1_1") (pintype "passive"))
    )
    (net (code "44") (name "Net-(RL8B-NC)") (class "Default")
      (node (ref "J106") (pin "4") (pinfunction "4_4") (pintype "bidirectional"))
      (node (ref "RL8") (pin "12") (pinfunction "NC_12") (pintype "bidirectional"))
    )
    (net (code "45") (name "Net-(RL8B-NO)") (class "Default")
      (node (ref "J106") (pin "2") (pinfunction "2_2") (pintype "bidirectional"))
      (node (ref "RL8") (pin "14") (pinfunction "NO_14") (pintype "bidirectional"))
    )
    (net (code "46") (name "P3V3") (class "Default")
      (node (ref "C286") (pin "2") (pinfunction "2_2") (pintype "passive"))
      (node (ref "C289") (pin "2") (pinfunction "2_2") (pintype "passive"))
      (node (ref "C290") (pin "2") (pinfunction "2_2") (pintype "passive"))
      (node (ref "C291") (pin "2") (pinfunction "2_2") (pintype "passive"))
      (node (ref "C292") (pin "2") (pinfunction "2_2") (pintype "passive"))
      (node (ref "IC100") (pin "8") (pinfunction "VCC_8") (pintype "power_in"))
      (node (ref "IC101") (pin "24") (pinfunction "VDD_24") (pintype "power_in"))
      (node (ref "IC101") (pin "36") (pinfunction "VDDIO2_36") (pintype "power_in"))
      (node (ref "IC101") (pin "48") (pinfunction "VDD_48") (pintype "power_in"))
      (node (ref "IC101") (pin "9") (pinfunction "VDDA_9") (pintype "power_in"))
      (node (ref "IC99") (pin "2") (pinfunction "OUT_2") (pintype "power_in"))
      (node (ref "JP10") (pin "1") (pinfunction "1_1") (pintype "passive"))
      (node (ref "R422") (pin "2") (pinfunction "2_2") (pintype "passive"))
      (node (ref "R425") (pin "2") (pinfunction "2_2") (pintype "passive"))
      (node (ref "R430") (pin "1") (pinfunction "1_1") (pintype "passive"))
      (node (ref "TP47") (pin "1") (pinfunction "1_1") (pintype "bidirectional"))
    )
    (net (code "47") (name "P5V0") (class "Default")
      (node (ref "C283") (pin "2") (pinfunction "2_2") (pintype "passive"))
      (node (ref "C284") (pin "2") (pinfunction "2_2") (pintype "passive"))
      (node (ref "C285") (pin "2") (pinfunction "2_2") (pintype "passive"))
      (node (ref "C288") (pin "1") (pinfunction "1_1") (pintype "passive"))
      (node (ref "C293") (pin "2") (pinfunction "2_2") (pintype "passive"))
      (node (ref "IC102") (pin "20") (pinfunction "VCC_20") (pintype "power_in"))
      (node (ref "IC103") (pin "8") (pinfunction "V+_8") (pintype "power_in"))
      (node (ref "IC97") (pin "3") (pinfunction "VDD_3") (pintype "power_in"))
      (node (ref "IC99") (pin "1") (pinfunction "IN_1") (pintype "input"))
      (node (ref "J105") (pin "5") (pinfunction "5_5") (pintype "bidirectional"))
      (node (ref "L15") (pin "2") (pinfunction "2_2") (pintype "passive"))
      (node (ref "R417") (pin "2") (pinfunction "2_2") (pintype "passive"))
      (node (ref "R429") (pin "1") (pinfunction "1_1") (pintype "passive"))
    )
    (net (code "48") (name "P12V0") (class "Default")
      (node (ref "D119") (pin "2") (pinfunction "A_2") (pintype "passive"))
      (node (ref "D120") (pin "1") (pinfunction "C_1") (pintype "passive"))
      (node (ref "J105") (pin "1") (pinfunction "1_1") (pintype "bidirectional"))
    )
    (net (code "49") (name "unconnected-(IC101-PA1-Pad11)") (class "Default")
      (node (ref "IC101") (pin "11") (pinfunction "PA1_11") (pintype "bidirectional"))
    )
    (net (code "50") (name "unconnected-(IC101-PA5-Pad15)") (class "Default")
      (node (ref "IC101") (pin "15") (pinfunction "PA5_15") (pintype "bidirectional"))
    )
    (net (code "51") (name "unconnected-(IC101-PA6-Pad16)") (class "Default")
      (node (ref "IC101") (pin "16") (pinfunction "PA6_16") (pintype "bidirectional"))
    )
    (net (code "52") (name "unconnected-(IC101-PA7-Pad17)") (class "Default")
      (node (ref "IC101") (pin "17") (pinfunction "PA7_17") (pintype "bidirectional"))
    )
    (net (code "53") (name "unconnected-(IC101-PA8-Pad29)") (class "Default")
      (node (ref "IC101") (pin "29") (pinfunction "PA8_29") (pintype "bidirectional"))
    )
    (net (code "54") (name "unconnected-(IC101-PA10-Pad31)") (class "Default")
      (node (ref "IC101") (pin "31") (pinfunction "PA10_31") (pintype "bidirectional"))
    )
    (net (code "55") (name "unconnected-(IC101-PA15-Pad38)") (class "Default")
      (node (ref "IC101") (pin "38") (pinfunction "PA15_38") (pintype "bidirectional"))
    )
    (net (code "56") (name "unconnected-(IC101-PB0-Pad18)") (class "Default")
      (node (ref "IC101") (pin "18") (pinfunction "PB0_18") (pintype "bidirectional"))
    )
    (net (code "57") (name "unconnected-(IC101-PB3-Pad39)") (class "Default")
      (node (ref "IC101") (pin "39") (pinfunction "PB3_39") (pintype "bidirectional"))
    )
    (net (code "58") (name "unconnected-(IC101-PB5-Pad41)") (class "Default")
      (node (ref "IC101") (pin "41") (pinfunction "PB5_41") (pintype "bidirectional"))
    )
    (net (code "59") (name "unconnected-(IC101-PB6-Pad42)") (class "Default")
      (node (ref "IC101") (pin "42") (pinfunction "PB6_42") (pintype "bidirectional"))
    )
    (net (code "60") (name "unconnected-(IC101-PB7-Pad43)") (class "Default")
      (node (ref "IC101") (pin "43") (pinfunction "PB7_43") (pintype "bidirectional"))
    )
    (net (code "61") (name "unconnected-(IC101-PB12-Pad25)") (class "Default")
      (node (ref "IC101") (pin "25") (pinfunction "PB12_25") (pintype "bidirectional"))
    )
    (net (code "62") (name "unconnected-(IC101-PB13-Pad26)") (class "Default")
      (node (ref "IC101") (pin "26") (pinfunction "PB13_26") (pintype "bidirectional"))
    )
    (net (code "63") (name "unconnected-(IC101-PB14-Pad27)") (class "Default")
      (node (ref "IC101") (pin "27") (pinfunction "PB14_27") (pintype "bidirectional"))
    )
    (net (code "64") (name "unconnected-(IC101-PB15-Pad28)") (class "Default")
      (node (ref "IC101") (pin "28") (pinfunction "PB15_28") (pintype "bidirectional"))
    )
    (net (code "65") (name "unconnected-(IC101-PC14-OSC32_IN(PC14)-Pad3)") (class "Default")
      (node (ref "IC101") (pin "3") (pinfunction "PC14-OSC32_IN(PC14)_3") (pintype "bidirectional"))
    )
    (net (code "66") (name "unconnected-(IC101-PC15-OSC32_OUT(PC15)-Pad4)") (class "Default")
      (node (ref "IC101") (pin "4") (pinfunction "PC15-OSC32_OUT(PC15)_4") (pintype "bidirectional"))
    )
    (net (code "67") (name "unconnected-(IC101-PF0-OSC_IN(PF0)-Pad5)") (class "Default")
      (node (ref "IC101") (pin "5") (pinfunction "PF0-OSC_IN(PF0)_5") (pintype "bidirectional"))
    )
    (net (code "68") (name "unconnected-(IC101-PF1-OSC_OUT(PF1)-Pad6)") (class "Default")
      (node (ref "IC101") (pin "6") (pinfunction "PF1-OSC_OUT(PF1)_6") (pintype "bidirectional"))
    )
    (net (code "69") (name "unconnected-(IC101-PF11-BOOT0-Pad44)") (class "Default")
      (node (ref "IC101") (pin "44") (pinfunction "PF11-BOOT0_44") (pintype "bidirectional"))
    )
    (net (code "70") (name "unconnected-(IC101-VBAT-Pad1)") (class "Default")
      (node (ref "IC101") (pin "1") (pinfunction "VBAT_1") (pintype "power_in"))
    )
    (net (code "71") (name "unconnected-(JP10-Pad6)") (class "Default")
      (node (ref "JP10") (pin "6") (pinfunction "6_6") (pintype "passive"))
    )
    (net (code "72") (name "unconnected-(JP10-Pad7)") (class "Default")
      (node (ref "JP10") (pin "7") (pinfunction "7_7") (pintype "passive"))
    )
    (net (code "73") (name "unconnected-(JP10-Pad8)") (class "Default")
      (node (ref "JP10") (pin "8") (pinfunction "8_8") (pintype "passive"))
    )
  )
)
